# AudioInOut.net
KiCad netlist of a schematic drawn in Altium Designer
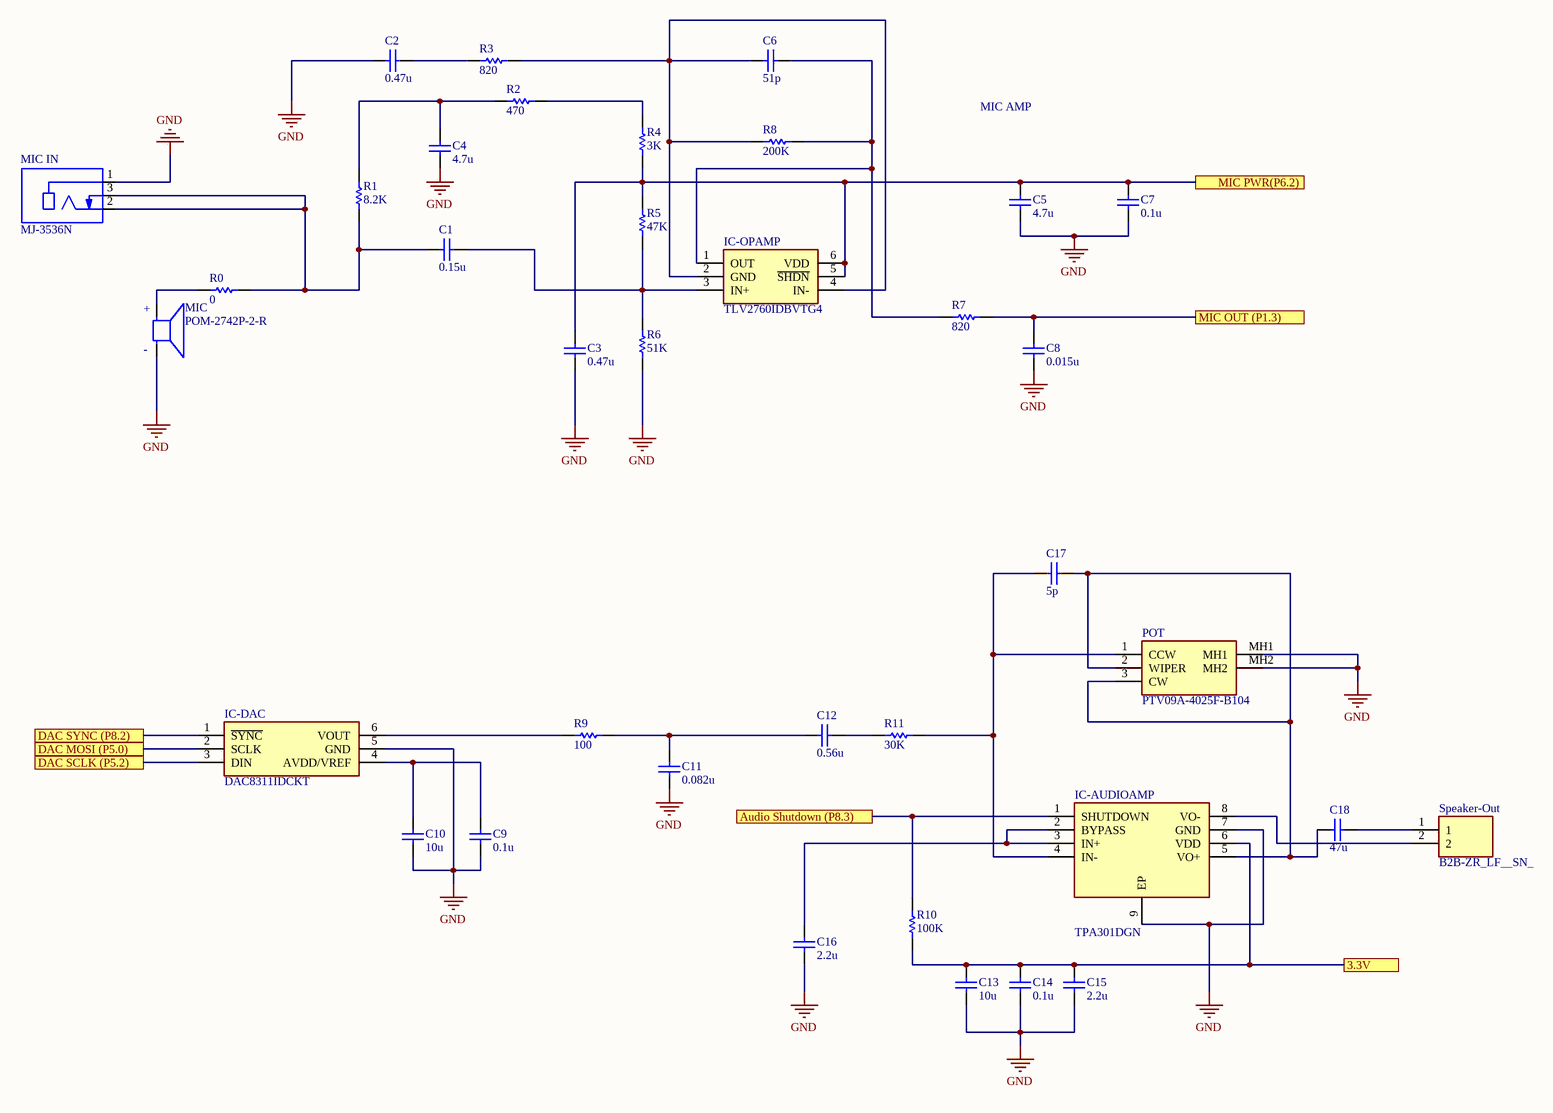
[diagram p0: AudioInOut.SchDoc]

(export (version "E")
  (design (tool "Eeschema 10.0.6"))
  (components
    (comp (ref "C1")
      (value "0.15u")
      (footprint "CAPC1206(3216)170_M")
      (description "CAP 6.8nF 50V ±10% 1206 (3216 Metric) Thickness 1.7mm SMD")
      (fields (field (name "TOLERANCE") "Â±10%"))
      (libsource (lib "Altium Content Vault") (part "CAP"))
    )
    (comp (ref "C2")
      (value "0.47u")
      (footprint "CAPC1206(3216)170_M")
      (description "CAP 6.8nF 50V ±10% 1206 (3216 Metric) Thickness 1.7mm SMD")
      (fields (field (name "TOLERANCE") "Â±10%"))
      (libsource (lib "Altium Content Vault") (part "CAP"))
    )
    (comp (ref "C3")
      (value "0.47u")
      (footprint "CAPC1206(3216)170_M")
      (description "CAP 6.8nF 50V ±10% 1206 (3216 Metric) Thickness 1.7mm SMD")
      (fields (field (name "TOLERANCE") "Â±10%"))
      (libsource (lib "Altium Content Vault") (part "CAP"))
    )
    (comp (ref "C4")
      (value "4.7u")
      (footprint "CAPC1206(3216)170_M")
      (description "CAP 6.8nF 50V ±10% 1206 (3216 Metric) Thickness 1.7mm SMD")
      (fields (field (name "TOLERANCE") "Â±10%"))
      (libsource (lib "Altium Content Vault") (part "CAP"))
    )
    (comp (ref "C5")
      (value "4.7u")
      (footprint "CAPC1206(3216)170_M")
      (description "CAP 6.8nF 50V ±10% 1206 (3216 Metric) Thickness 1.7mm SMD")
      (fields (field (name "TOLERANCE") "Â±10%"))
      (libsource (lib "Altium Content Vault") (part "CAP"))
    )
    (comp (ref "C6")
      (value "51p")
      (footprint "CAPC1206(3216)170_M")
      (description "CAP 6.8nF 50V ±10% 1206 (3216 Metric) Thickness 1.7mm SMD")
      (fields (field (name "TOLERANCE") "Â±10%"))
      (libsource (lib "Altium Content Vault") (part "CAP"))
    )
    (comp (ref "C7")
      (value "0.1u")
      (footprint "CAPC1206(3216)170_M")
      (description "CAP 6.8nF 50V ±10% 1206 (3216 Metric) Thickness 1.7mm SMD")
      (fields (field (name "TOLERANCE") "Â±10%"))
      (libsource (lib "Altium Content Vault") (part "CAP"))
    )
    (comp (ref "C8")
      (value "0.015u")
      (footprint "CAPC1206(3216)170_M")
      (description "CAP 6.8nF 50V ±10% 1206 (3216 Metric) Thickness 1.7mm SMD")
      (fields (field (name "TOLERANCE") "Â±10%"))
      (libsource (lib "Altium Content Vault") (part "CAP"))
    )
    (comp (ref "C9")
      (value "0.1u")
      (footprint "CAPC1206(3216)170_M")
      (description "CAP 6.8nF 50V ±10% 1206 (3216 Metric) Thickness 1.7mm SMD")
      (fields (field (name "TOLERANCE") "Â±10%"))
      (libsource (lib "Altium Content Vault") (part "CAP"))
    )
    (comp (ref "C10")
      (value "10u")
      (footprint "CAPC1206(3216)170_M")
      (description "CAP 6.8nF 50V ±10% 1206 (3216 Metric) Thickness 1.7mm SMD")
      (fields (field (name "TOLERANCE") "Â±10%"))
      (libsource (lib "Altium Content Vault") (part "CAP"))
    )
    (comp (ref "C11")
      (value "0.082u")
      (footprint "CAPC1206(3216)170_M")
      (description "CAP 6.8nF 50V ±10% 1206 (3216 Metric) Thickness 1.7mm SMD")
      (fields (field (name "TOLERANCE") "Â±10%"))
      (libsource (lib "Altium Content Vault") (part "CAP"))
    )
    (comp (ref "C12")
      (value "0.56u")
      (footprint "CAPC1206(3216)170_M")
      (description "CAP 6.8nF 50V ±10% 1206 (3216 Metric) Thickness 1.7mm SMD")
      (fields (field (name "TOLERANCE") "Â±10%"))
      (libsource (lib "Altium Content Vault") (part "CAP"))
    )
    (comp (ref "C13")
      (value "10u")
      (footprint "CAPC1206(3216)170_M")
      (description "CAP 6.8nF 50V ±10% 1206 (3216 Metric) Thickness 1.7mm SMD")
      (fields (field (name "TOLERANCE") "Â±10%"))
      (libsource (lib "Altium Content Vault") (part "CAP"))
    )
    (comp (ref "C14")
      (value "0.1u")
      (footprint "CAPC1206(3216)170_M")
      (description "CAP 6.8nF 50V ±10% 1206 (3216 Metric) Thickness 1.7mm SMD")
      (fields (field (name "TOLERANCE") "Â±10%"))
      (libsource (lib "Altium Content Vault") (part "CAP"))
    )
    (comp (ref "C15")
      (value "2.2u")
      (footprint "CAPC1206(3216)170_M")
      (description "CAP 6.8nF 50V ±10% 1206 (3216 Metric) Thickness 1.7mm SMD")
      (fields (field (name "TOLERANCE") "Â±10%"))
      (libsource (lib "Altium Content Vault") (part "CAP"))
    )
    (comp (ref "C16")
      (value "2.2u")
      (footprint "CAPC1206(3216)170_M")
      (description "CAP 6.8nF 50V ±10% 1206 (3216 Metric) Thickness 1.7mm SMD")
      (fields (field (name "TOLERANCE") "Â±10%"))
      (libsource (lib "Altium Content Vault") (part "CAP"))
    )
    (comp (ref "C17")
      (value "5p")
      (footprint "CAPC1206(3216)170_M")
      (description "CAP 6.8nF 50V ±10% 1206 (3216 Metric) Thickness 1.7mm SMD")
      (fields (field (name "TOLERANCE") "Â±10%"))
      (libsource (lib "Altium Content Vault") (part "CAP"))
    )
    (comp (ref "C18")
      (value "47u")
      (footprint "CAPC1206(3216)170_M")
      (description "CAP 6.8nF 50V ±10% 1206 (3216 Metric) Thickness 1.7mm SMD")
      (fields (field (name "TOLERANCE") "Â±10%"))
      (libsource (lib "Altium Content Vault") (part "CAP"))
    )
    (comp (ref "IC-AUDIOAMP")
      (value "TPA301DGN")
      (footprint "SamacSys:SOP65P490X110-9N")
      (description "Integrated Circuit")
      (fields (field (name "MOUSER2 PART NUMBER") "595-TPA301DGN"))
      (libsource (lib "*") (part "TPA301DGN"))
    )
    (comp (ref "IC-DAC")
      (value "DAC8311IDCKT")
      (footprint "SamacSys:SOT65P210X110-6N")
      (description "Integrated Circuit")
      (fields (field (name "MOUSER2 PART NUMBER") "595-DAC8311IDCKT"))
      (libsource (lib "*") (part "DAC8311IDCKT"))
    )
    (comp (ref "IC-OPAMP")
      (value "TLV2760IDBVTG4")
      (footprint "SamacSys:SOT95P280X145-6N")
      (description "Integrated Circuit")
      (fields (field (name "MOUSER2 PART NUMBER") "595-TLV2760IDBVTG4"))
      (libsource (lib "*") (part "TLV2760IDBVTG4"))
    )
    (comp (ref "MIC")
      (value "POM-2742P-2-R")
      (footprint "MIC_POM-2742P-2-R")
      (description "ELECTRET CONDENSER MICROPHONE 6MM DIA")
      (fields (field (name "MF") "PUI Audio") (field (name "DIGI-KEY_PART_NUMBER") "668-1160-ND"))
      (libsource (lib "POM-2742P-2-R") (part "POM-2742P-2-R"))
    )
    (comp (ref "MIC IN")
      (value "MJ-3536N")
      (footprint "CUI_MJ-3536N")
      (description "3.5 mm, Mono, Right Angle, Through Hole, Audio Jack Connector")
      (fields (field (name "MF") "CUI Devices"))
      (libsource (lib "MJ-3536N (1)") (part "MJ-3536N"))
    )
    (comp (ref "POT")
      (value "PTV09A-4025F-B104")
      (footprint "SamacSys:PTV09A4025FB104")
      (description "Variable Resistor")
      (fields (field (name "MOUSER2 PART NUMBER") "652-PTV09A4025FB104"))
      (libsource (lib "*") (part "PTV09A-4025F-B104"))
    )
    (comp (ref "R0")
      (value "0")
      (footprint "RESC3216X60X45NL10T20")
      (fields (field (name "PART NUMBER") "CRCW1206470KFKEA") (field (name "MANUFACTURER") "Vishay Dale"))
      (libsource (lib "Altium Content Vault") (part "RES"))
    )
    (comp (ref "R1")
      (value "8.2K")
      (footprint "RESC3216X60X45NL10T20")
      (fields (field (name "PART NUMBER") "CRCW1206470KFKEA") (field (name "MANUFACTURER") "Vishay Dale"))
      (libsource (lib "Altium Content Vault") (part "RES"))
    )
    (comp (ref "R2")
      (value "470")
      (footprint "RESC3216X60X45NL10T20")
      (fields (field (name "PART NUMBER") "CRCW1206470KFKEA") (field (name "MANUFACTURER") "Vishay Dale"))
      (libsource (lib "Altium Content Vault") (part "RES"))
    )
    (comp (ref "R3")
      (value "820")
      (footprint "RESC3216X60X45NL10T20")
      (fields (field (name "PART NUMBER") "CRCW1206470KFKEA") (field (name "MANUFACTURER") "Vishay Dale"))
      (libsource (lib "Altium Content Vault") (part "RES"))
    )
    (comp (ref "R4")
      (value "3K")
      (footprint "RESC3216X70X50LL05T20")
      (fields (field (name "MANUFACTURER") "Panasonic") (field (name "PART NUMBER") "ERJ8ENF3001V"))
      (libsource (lib "Altium Content Vault") (part "RES"))
    )
    (comp (ref "R5")
      (value "47K")
      (footprint "RESC3216X60X45LL10T20")
      (fields (field (name "PART NUMBER") "CRCW120647K0FKEA") (field (name "MANUFACTURER") "Vishay Dale"))
      (libsource (lib "Altium Content Vault") (part "RES"))
    )
    (comp (ref "R6")
      (value "51K")
      (footprint "RESC3216X70X50NL20T25")
      (fields (field (name "MANUFACTURER") "Panasonic") (field (name "PART NUMBER") "ERA8AEB513V"))
      (libsource (lib "Altium Content Vault") (part "RES"))
    )
    (comp (ref "R7")
      (value "820")
      (footprint "RESC3216X60X45NL10T20")
      (fields (field (name "PART NUMBER") "CRCW1206470KFKEA") (field (name "MANUFACTURER") "Vishay Dale"))
      (libsource (lib "Altium Content Vault") (part "RES"))
    )
    (comp (ref "R8")
      (value "200K")
      (footprint "RESC3216X60X45NL10T20")
      (fields (field (name "PART NUMBER") "CRCW1206470KFKEA") (field (name "MANUFACTURER") "Vishay Dale"))
      (libsource (lib "Altium Content Vault") (part "RES"))
    )
    (comp (ref "R9")
      (value "100")
      (footprint "RESC3216X60X45NL10T20")
      (fields (field (name "PART NUMBER") "CRCW1206470KFKEA") (field (name "MANUFACTURER") "Vishay Dale"))
      (libsource (lib "Altium Content Vault") (part "RES"))
    )
    (comp (ref "R10")
      (value "100K")
      (footprint "RESC3216X60X45NL10T20")
      (fields (field (name "PART NUMBER") "CRCW1206470KFKEA") (field (name "MANUFACTURER") "Vishay Dale"))
      (libsource (lib "Altium Content Vault") (part "RES"))
    )
    (comp (ref "R11")
      (value "30K")
      (footprint "RESC3216X60X45NL10T20")
      (fields (field (name "PART NUMBER") "CRCW1206470KFKEA") (field (name "MANUFACTURER") "Vishay Dale"))
      (libsource (lib "Altium Content Vault") (part "RES"))
    )
    (comp (ref "Speaker-Out")
      (value "B2B-ZR_LF__SN_")
      (footprint "SamacSys:SHDR2W50P0X150_1X2_450X350X450P")
      (description "Connector")
      (fields (field (name "MANUFACTURER_PART_NUMBER") "B2B-ZR(LF)(SN)"))
      (libsource (lib "*") (part "B2B-ZR_LF__SN_"))
    )
  )
  (nets
    (net (code "1") (name "/3.3V") (class "Default")
      (node (ref "C13") (pin "1") (pinfunction "1_1") (pintype "passive"))
      (node (ref "C14") (pin "1") (pinfunction "1_1") (pintype "passive"))
      (node (ref "C15") (pin "1") (pinfunction "1_1") (pintype "passive"))
      (node (ref "IC-AUDIOAMP") (pin "6") (pinfunction "VDD_6") (pintype "passive"))
      (node (ref "R10") (pin "1") (pinfunction "1_1") (pintype "passive"))
    )
    (net (code "2") (name "/Audio Shutdown (P8.3)") (class "Default")
      (node (ref "IC-AUDIOAMP") (pin "1") (pinfunction "SHUTDOWN_1") (pintype "passive"))
      (node (ref "R10") (pin "2") (pinfunction "2_2") (pintype "passive"))
    )
    (net (code "3") (name "/DAC MOSI (P5.0)") (class "Default")
      (node (ref "IC-DAC") (pin "2") (pinfunction "SCLK_2") (pintype "passive"))
    )
    (net (code "4") (name "/DAC SCLK (P5.2)") (class "Default")
      (node (ref "IC-DAC") (pin "3") (pinfunction "DIN_3") (pintype "passive"))
    )
    (net (code "5") (name "/DAC SYNC (P8.2)") (class "Default")
      (node (ref "IC-DAC") (pin "1") (pinfunction "~{SYNC}_1") (pintype "passive"))
    )
    (net (code "6") (name "/MIC OUT (P1.3)") (class "Default")
      (node (ref "C8") (pin "1") (pinfunction "1_1") (pintype "passive"))
      (node (ref "R7") (pin "1") (pinfunction "1_1") (pintype "passive"))
    )
    (net (code "7") (name "/MIC PWR(P6.2)") (class "Default")
      (node (ref "C3") (pin "1") (pinfunction "1_1") (pintype "passive"))
      (node (ref "C5") (pin "1") (pinfunction "1_1") (pintype "passive"))
      (node (ref "C7") (pin "1") (pinfunction "1_1") (pintype "passive"))
      (node (ref "IC-OPAMP") (pin "5") (pinfunction "~{SHDN}_5") (pintype "passive"))
      (node (ref "IC-OPAMP") (pin "6") (pinfunction "VDD_6") (pintype "passive"))
      (node (ref "R4") (pin "1") (pinfunction "1_1") (pintype "passive"))
      (node (ref "R5") (pin "2") (pinfunction "2_2") (pintype "passive"))
    )
    (net (code "8") (name "GND") (class "Default")
      (node (ref "C10") (pin "2") (pinfunction "2_2") (pintype "passive"))
      (node (ref "C11") (pin "2") (pinfunction "2_2") (pintype "passive"))
      (node (ref "C13") (pin "2") (pinfunction "2_2") (pintype "passive"))
      (node (ref "C14") (pin "2") (pinfunction "2_2") (pintype "passive"))
      (node (ref "C15") (pin "2") (pinfunction "2_2") (pintype "passive"))
      (node (ref "C16") (pin "2") (pinfunction "2_2") (pintype "passive"))
      (node (ref "C2") (pin "1") (pinfunction "1_1") (pintype "passive"))
      (node (ref "C3") (pin "2") (pinfunction "2_2") (pintype "passive"))
      (node (ref "C4") (pin "2") (pinfunction "2_2") (pintype "passive"))
      (node (ref "C5") (pin "2") (pinfunction "2_2") (pintype "passive"))
      (node (ref "C7") (pin "2") (pinfunction "2_2") (pintype "passive"))
      (node (ref "C8") (pin "2") (pinfunction "2_2") (pintype "passive"))
      (node (ref "C9") (pin "2") (pinfunction "2_2") (pintype "passive"))
      (node (ref "IC-AUDIOAMP") (pin "7") (pinfunction "GND_7") (pintype "passive"))
      (node (ref "IC-AUDIOAMP") (pin "9") (pinfunction "EP_9") (pintype "passive"))
      (node (ref "IC-DAC") (pin "5") (pinfunction "GND_5") (pintype "passive"))
      (node (ref "MIC") (pin "N") (pinfunction "NEG_N") (pintype "passive"))
      (node (ref "MIC IN") (pin "1") (pinfunction "1_1") (pintype "passive"))
      (node (ref "POT") (pin "MH1") (pinfunction "MH1_MH1") (pintype "passive"))
      (node (ref "POT") (pin "MH2") (pinfunction "MH2_MH2") (pintype "passive"))
      (node (ref "R6") (pin "1") (pinfunction "1_1") (pintype "passive"))
    )
    (net (code "9") (name "Net-(C1-Pad1)") (class "Default")
      (node (ref "C1") (pin "1") (pinfunction "1_1") (pintype "passive"))
      (node (ref "MIC IN") (pin "2") (pinfunction "2_2") (pintype "passive"))
      (node (ref "MIC IN") (pin "3") (pinfunction "3_3") (pintype "passive"))
      (node (ref "R0") (pin "1") (pinfunction "1_1") (pintype "passive"))
      (node (ref "R1") (pin "1") (pinfunction "1_1") (pintype "passive"))
    )
    (net (code "10") (name "Net-(C2-Pad2)") (class "Default")
      (node (ref "C2") (pin "2") (pinfunction "2_2") (pintype "passive"))
      (node (ref "R3") (pin "1") (pinfunction "1_1") (pintype "passive"))
    )
    (net (code "11") (name "Net-(C4-Pad1)") (class "Default")
      (node (ref "C4") (pin "1") (pinfunction "1_1") (pintype "passive"))
      (node (ref "R1") (pin "2") (pinfunction "2_2") (pintype "passive"))
      (node (ref "R2") (pin "1") (pinfunction "1_1") (pintype "passive"))
    )
    (net (code "12") (name "Net-(C11-Pad1)") (class "Default")
      (node (ref "C11") (pin "1") (pinfunction "1_1") (pintype "passive"))
      (node (ref "C12") (pin "1") (pinfunction "1_1") (pintype "passive"))
      (node (ref "R9") (pin "2") (pinfunction "2_2") (pintype "passive"))
    )
    (net (code "13") (name "Net-(C12-Pad2)") (class "Default")
      (node (ref "C12") (pin "2") (pinfunction "2_2") (pintype "passive"))
      (node (ref "R11") (pin "1") (pinfunction "1_1") (pintype "passive"))
    )
    (net (code "14") (name "Net-(C18-Pad2)") (class "Default")
      (node (ref "C18") (pin "2") (pinfunction "2_2") (pintype "passive"))
      (node (ref "Speaker-Out") (pin "1") (pinfunction "1_1") (pintype "passive"))
    )
    (net (code "15") (name "Net-(IC-AUDIOAMP-BYPASS)") (class "Default")
      (node (ref "C16") (pin "1") (pinfunction "1_1") (pintype "passive"))
      (node (ref "IC-AUDIOAMP") (pin "2") (pinfunction "BYPASS_2") (pintype "passive"))
      (node (ref "IC-AUDIOAMP") (pin "3") (pinfunction "IN+_3") (pintype "passive"))
    )
    (net (code "16") (name "Net-(IC-AUDIOAMP-IN-)") (class "Default")
      (node (ref "C17") (pin "1") (pinfunction "1_1") (pintype "passive"))
      (node (ref "IC-AUDIOAMP") (pin "4") (pinfunction "IN-_4") (pintype "passive"))
      (node (ref "POT") (pin "1") (pinfunction "CCW_1") (pintype "passive"))
      (node (ref "R11") (pin "2") (pinfunction "2_2") (pintype "passive"))
    )
    (net (code "17") (name "Net-(IC-AUDIOAMP-VO+)") (class "Default")
      (node (ref "C17") (pin "2") (pinfunction "2_2") (pintype "passive"))
      (node (ref "C18") (pin "1") (pinfunction "1_1") (pintype "passive"))
      (node (ref "IC-AUDIOAMP") (pin "5") (pinfunction "VO+_5") (pintype "passive"))
      (node (ref "POT") (pin "2") (pinfunction "WIPER_2") (pintype "passive"))
      (node (ref "POT") (pin "3") (pinfunction "CW_3") (pintype "passive"))
    )
    (net (code "18") (name "Net-(IC-AUDIOAMP-VO-)") (class "Default")
      (node (ref "IC-AUDIOAMP") (pin "8") (pinfunction "VO-_8") (pintype "passive"))
      (node (ref "Speaker-Out") (pin "2") (pinfunction "2_2") (pintype "passive"))
    )
    (net (code "19") (name "Net-(IC-DAC-AVDD{slash}VREF)") (class "Default")
      (node (ref "C10") (pin "1") (pinfunction "1_1") (pintype "passive"))
      (node (ref "C9") (pin "1") (pinfunction "1_1") (pintype "passive"))
      (node (ref "IC-DAC") (pin "4") (pinfunction "AVDD/VREF_4") (pintype "passive"))
    )
    (net (code "20") (name "Net-(IC-DAC-VOUT)") (class "Default")
      (node (ref "IC-DAC") (pin "6") (pinfunction "VOUT_6") (pintype "passive"))
      (node (ref "R9") (pin "1") (pinfunction "1_1") (pintype "passive"))
    )
    (net (code "21") (name "Net-(IC-OPAMP-GND)") (class "Default")
      (node (ref "C6") (pin "1") (pinfunction "1_1") (pintype "passive"))
      (node (ref "IC-OPAMP") (pin "2") (pinfunction "GND_2") (pintype "passive"))
      (node (ref "IC-OPAMP") (pin "4") (pinfunction "IN-_4") (pintype "passive"))
      (node (ref "R3") (pin "2") (pinfunction "2_2") (pintype "passive"))
      (node (ref "R8") (pin "1") (pinfunction "1_1") (pintype "passive"))
    )
    (net (code "22") (name "Net-(IC-OPAMP-IN+)") (class "Default")
      (node (ref "C1") (pin "2") (pinfunction "2_2") (pintype "passive"))
      (node (ref "IC-OPAMP") (pin "3") (pinfunction "IN+_3") (pintype "passive"))
      (node (ref "R5") (pin "1") (pinfunction "1_1") (pintype "passive"))
      (node (ref "R6") (pin "2") (pinfunction "2_2") (pintype "passive"))
    )
    (net (code "23") (name "Net-(IC-OPAMP-OUT)") (class "Default")
      (node (ref "C6") (pin "2") (pinfunction "2_2") (pintype "passive"))
      (node (ref "IC-OPAMP") (pin "1") (pinfunction "OUT_1") (pintype "passive"))
      (node (ref "R7") (pin "2") (pinfunction "2_2") (pintype "passive"))
      (node (ref "R8") (pin "2") (pinfunction "2_2") (pintype "passive"))
    )
    (net (code "24") (name "Net-(MIC-POS)") (class "Default")
      (node (ref "MIC") (pin "P") (pinfunction "POS_P") (pintype "passive"))
      (node (ref "R0") (pin "2") (pinfunction "2_2") (pintype "passive"))
    )
    (net (code "25") (name "Net-(R2-Pad2)") (class "Default")
      (node (ref "R2") (pin "2") (pinfunction "2_2") (pintype "passive"))
      (node (ref "R4") (pin "2") (pinfunction "2_2") (pintype "passive"))
    )
  )
)
